# SCH_Hacker-Card-First_2024-08-30.net
KiCad netlist of a schematic drawn in EasyEDA
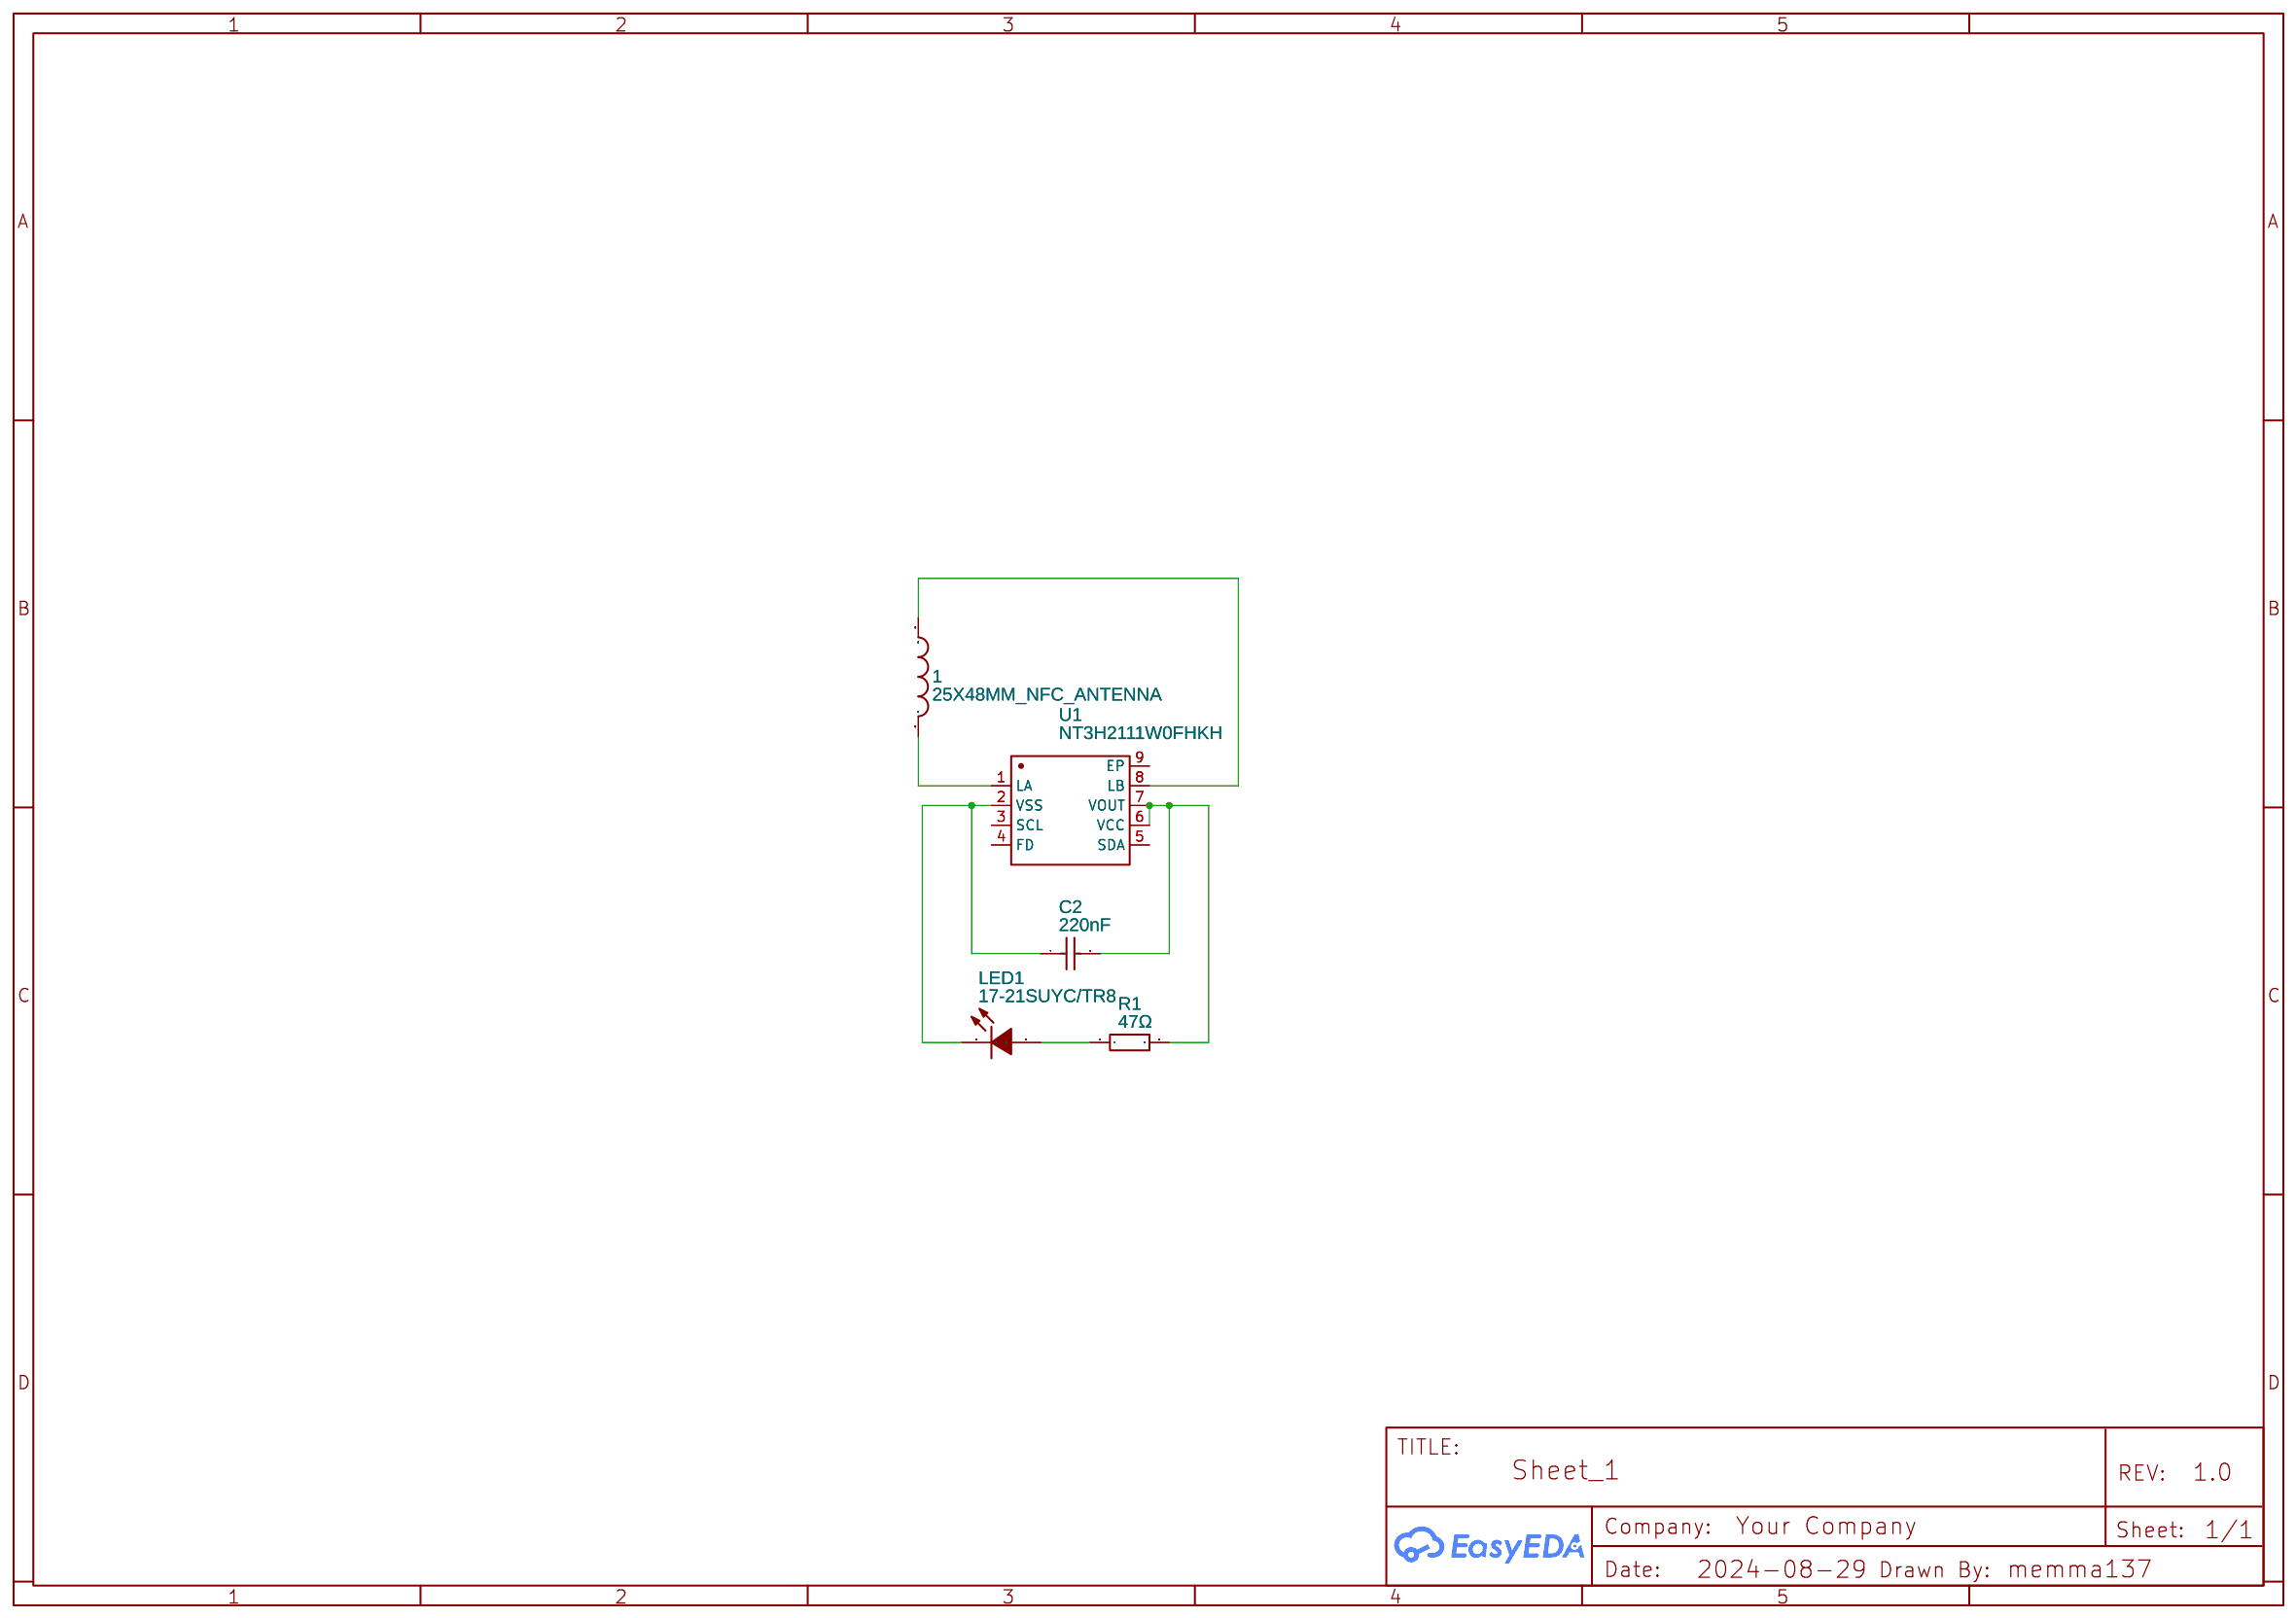
[diagram p0: schematic sheet]

(export (version "E")
  (design (tool "Eeschema 10.0.6"))
  (components
    (comp (ref "1") (value "25X48MM_NFC_ANTENNA") (libsource (lib "") (part "25X48MM_NFC_ANTENNA")))
    (comp (ref "C2")
      (value "220nF")
      (fields
        (field (name "Manufacturer Part") "CL10B224KA8NNNC")
        (field (name "Manufacturer") "SAMSUNG(三星)")
      )
      (libsource (lib "") (part "CL10B224KA8NNNC"))
    )
    (comp (ref "LED1")
      (value "17-21SUYC/TR8")
      (fields (field (name "Manufacturer Part") "KT-0805黄灯") (field (name "Manufacturer") "KENTO"))
      (libsource (lib "") (part "17-21SUYC/TR8"))
    )
    (comp (ref "R1")
      (value "47Ω")
      (fields
        (field (name "Manufacturer Part") "0603WAF470JT5E")
        (field (name "Manufacturer") "UNI-ROYAL(厚声)")
      )
      (libsource (lib "") (part "0603WAF470JT5E"))
    )
    (comp (ref "U1")
      (value "NT3H2111W0FHKH")
      (fields (field (name "Manufacturer") "NXP(恩智浦)"))
      (libsource (lib "") (part "NT3H2111W0FHKH"))
    )
  )
  (nets
    (net (code "1") (name "Net-(LED1-+)") (class "Default")
      (node (ref "LED1") (pin "1") (pinfunction "+_1") (pintype "unspecified"))
      (node (ref "R1") (pin "1") (pinfunction "1_1") (pintype "input"))
    )
    (net (code "2") (name "Net-(LED1--)") (class "Default")
      (node (ref "C2") (pin "1") (pinfunction "1_1") (pintype "input"))
      (node (ref "LED1") (pin "2") (pinfunction "-_2") (pintype "unspecified"))
      (node (ref "U1") (pin "2") (pinfunction "VSS_2") (pintype "unspecified"))
    )
    (net (code "3") (name "Net-(U1-LA)") (class "Default")
      (node (ref "1") (pin "P$2") (pinfunction "P$2_P$2") (pintype "bidirectional"))
      (node (ref "U1") (pin "1") (pinfunction "LA_1") (pintype "unspecified"))
    )
    (net (code "4") (name "Net-(U1-LB)") (class "Default")
      (node (ref "1") (pin "P$1") (pinfunction "P$1_P$1") (pintype "bidirectional"))
      (node (ref "U1") (pin "8") (pinfunction "LB_8") (pintype "unspecified"))
    )
    (net (code "5") (name "Net-(U1-VCC)") (class "Default")
      (node (ref "C2") (pin "2") (pinfunction "2_2") (pintype "input"))
      (node (ref "R1") (pin "2") (pinfunction "2_2") (pintype "input"))
      (node (ref "U1") (pin "6") (pinfunction "VCC_6") (pintype "unspecified"))
      (node (ref "U1") (pin "7") (pinfunction "VOUT_7") (pintype "unspecified"))
    )
    (net (code "6") (name "unconnected-(U1-EP-Pad9)") (class "Default")
      (node (ref "U1") (pin "9") (pinfunction "EP_9") (pintype "unspecified"))
    )
    (net (code "7") (name "unconnected-(U1-FD-Pad4)") (class "Default")
      (node (ref "U1") (pin "4") (pinfunction "FD_4") (pintype "unspecified"))
    )
    (net (code "8") (name "unconnected-(U1-SCL-Pad3)") (class "Default")
      (node (ref "U1") (pin "3") (pinfunction "SCL_3") (pintype "unspecified"))
    )
    (net (code "9") (name "unconnected-(U1-SDA-Pad5)") (class "Default")
      (node (ref "U1") (pin "5") (pinfunction "SDA_5") (pintype "unspecified"))
    )
  )
)
